# Game_of_Life_v1.net
KiCad netlist of a schematic drawn in EAGLE
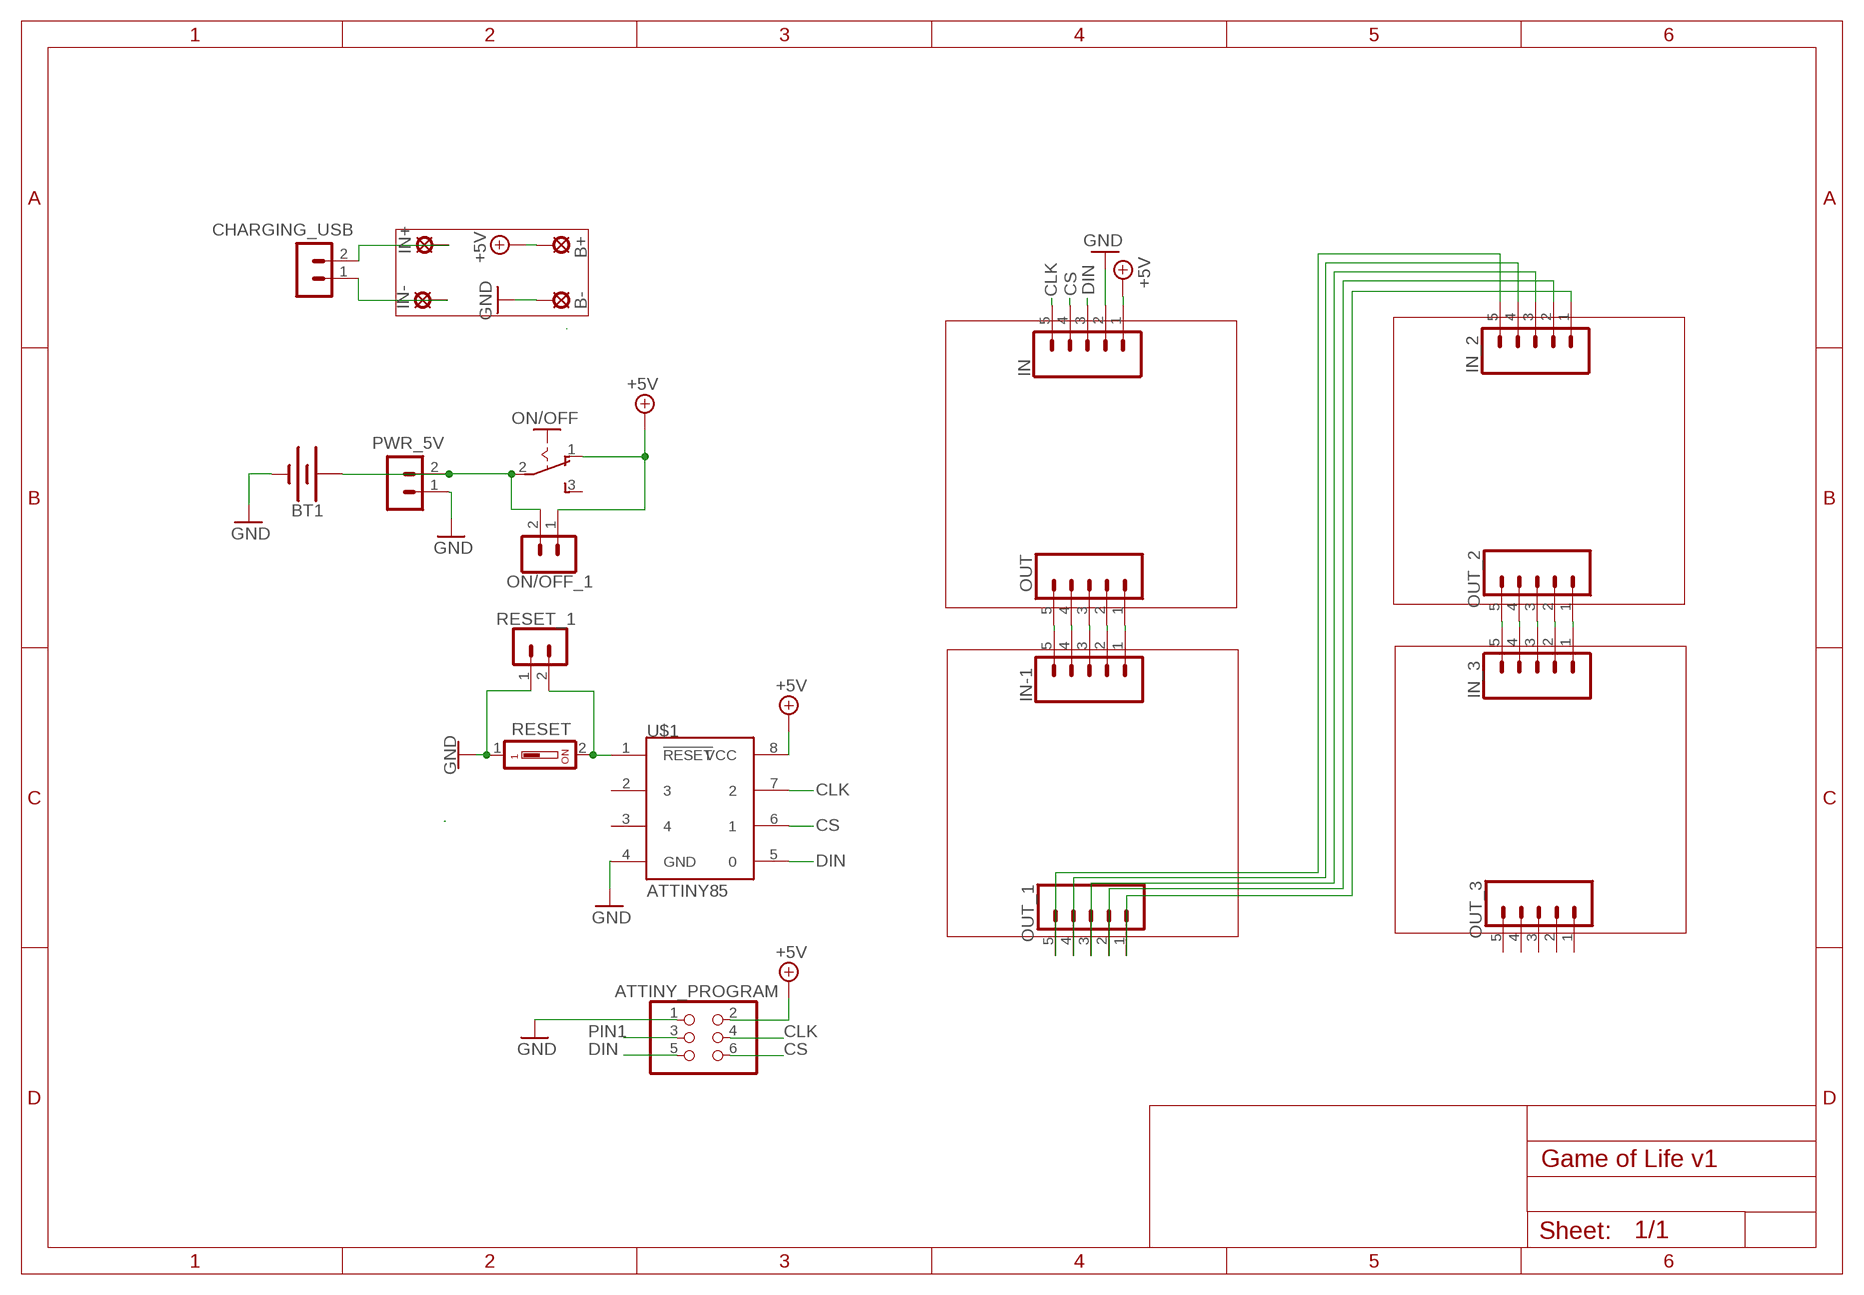
[diagram p0: schematic, sheet 1]

(export (version "E")
  (design (tool "Eeschema 10.0.6"))
  (components
    (comp (ref "ATTINY_PROGRAM")
      (value "PINHD-2X3")
      (footprint "eagle-import:2X03")
      (libsource (lib "eagle-import") (part "PINHD-2X3"))
    )
    (comp (ref "B+")
      (value "LSP11")
      (footprint "eagle-import:LSP11")
      (libsource (lib "eagle-import") (part "LSP11"))
    )
    (comp (ref "B-")
      (value "LSP11")
      (footprint "eagle-import:LSP11")
      (libsource (lib "eagle-import") (part "LSP11"))
    )
    (comp (ref "BT1")
      (value "BATTERY-18650")
      (footprint "eagle-import:BATTERY_18650-HOLDER")
      (libsource (lib "eagle-import") (part "BATTERY-18650"))
    )
    (comp (ref "CHARGING_USB")
      (value "B2B-PH-K-S")
      (footprint "eagle-import:B2B-PH-K-S")
      (libsource (lib "eagle-import") (part "B2B-PH-K-S"))
    )
    (comp (ref "IN")
      (value "CONN_05")
      (footprint "eagle-import:1X05")
      (libsource (lib "eagle-import") (part "CONN_05"))
    )
    (comp (ref "IN+")
      (value "LSP11")
      (footprint "eagle-import:LSP11")
      (libsource (lib "eagle-import") (part "LSP11"))
    )
    (comp (ref "IN-")
      (value "LSP11")
      (footprint "eagle-import:LSP11")
      (libsource (lib "eagle-import") (part "LSP11"))
    )
    (comp (ref "IN-1")
      (value "CONN_05")
      (footprint "eagle-import:1X05")
      (libsource (lib "eagle-import") (part "CONN_05"))
    )
    (comp (ref "IN_2")
      (value "CONN_05")
      (footprint "eagle-import:1X05")
      (libsource (lib "eagle-import") (part "CONN_05"))
    )
    (comp (ref "IN_3")
      (value "CONN_05")
      (footprint "eagle-import:1X05")
      (libsource (lib "eagle-import") (part "CONN_05"))
    )
    (comp (ref "ON/OFF")
      (value "M251")
      (footprint "eagle-import:M251")
      (libsource (lib "eagle-import") (part "M251"))
    )
    (comp (ref "ON/OFF_1")
      (value "B2B-PH-K-S")
      (footprint "eagle-import:B2B-PH-K-S")
      (libsource (lib "eagle-import") (part "B2B-PH-K-S"))
    )
    (comp (ref "OUT")
      (value "CONN_05")
      (footprint "eagle-import:1X05")
      (libsource (lib "eagle-import") (part "CONN_05"))
    )
    (comp (ref "OUT_1")
      (value "CONN_05")
      (footprint "eagle-import:1X05")
      (libsource (lib "eagle-import") (part "CONN_05"))
    )
    (comp (ref "OUT_2")
      (value "CONN_05")
      (footprint "eagle-import:1X05")
      (libsource (lib "eagle-import") (part "CONN_05"))
    )
    (comp (ref "OUT_3")
      (value "CONN_05")
      (footprint "eagle-import:1X05")
      (libsource (lib "eagle-import") (part "CONN_05"))
    )
    (comp (ref "PWR_5V")
      (value "B2B-PH-K-S")
      (footprint "eagle-import:B2B-PH-K-S")
      (libsource (lib "eagle-import") (part "B2B-PH-K-S"))
    )
    (comp (ref "RESET")
      (value "DS01")
      (footprint "eagle-import:DS-01")
      (libsource (lib "eagle-import") (part "DS01"))
    )
    (comp (ref "RESET_1")
      (value "B2B-PH-K-S")
      (footprint "eagle-import:B2B-PH-K-S")
      (libsource (lib "eagle-import") (part "B2B-PH-K-S"))
    )
    (comp (ref "U$1")
      (value "ATTINY85")
      (footprint "eagle-import:8P3")
      (libsource (lib "eagle-import") (part "ATTINY85"))
    )
  )
  (nets
    (net (code "1") (name "+5V") (class "Default")
      (node (ref "ATTINY_PROGRAM") (pin "2") (pinfunction "2_2") (pintype "passive"))
      (node (ref "B+") (pin "MP") (pinfunction "MP_MP") (pintype "passive"))
      (node (ref "IN") (pin "1") (pinfunction "1_1") (pintype "passive"))
      (node (ref "ON/OFF") (pin "1") (pinfunction "O_1") (pintype "passive"))
      (node (ref "ON/OFF_1") (pin "1") (pinfunction "1_1") (pintype "passive"))
      (node (ref "U$1") (pin "8") (pinfunction "VCC_8") (pintype "power_in"))
    )
    (net (code "2") (name "/CLK") (class "Default")
      (node (ref "ATTINY_PROGRAM") (pin "4") (pinfunction "4_4") (pintype "passive"))
      (node (ref "IN") (pin "5") (pinfunction "5_5") (pintype "passive"))
      (node (ref "U$1") (pin "7") (pinfunction "2_7") (pintype "bidirectional"))
    )
    (net (code "3") (name "/CS") (class "Default")
      (node (ref "ATTINY_PROGRAM") (pin "6") (pinfunction "6_6") (pintype "passive"))
      (node (ref "IN") (pin "4") (pinfunction "4_4") (pintype "passive"))
      (node (ref "U$1") (pin "6") (pinfunction "1_6") (pintype "bidirectional"))
    )
    (net (code "4") (name "/DIN") (class "Default")
      (node (ref "ATTINY_PROGRAM") (pin "5") (pinfunction "5_5") (pintype "passive"))
      (node (ref "IN") (pin "3") (pinfunction "3_3") (pintype "passive"))
      (node (ref "U$1") (pin "5") (pinfunction "0_5") (pintype "bidirectional"))
    )
    (net (code "5") (name "/PIN1") (class "Default")
      (node (ref "ATTINY_PROGRAM") (pin "3") (pinfunction "3_3") (pintype "passive"))
      (node (ref "RESET") (pin "2") (pinfunction "2_2") (pintype "passive"))
      (node (ref "RESET_1") (pin "2") (pinfunction "2_2") (pintype "passive"))
      (node (ref "U$1") (pin "1") (pinfunction "~{RESET}_1") (pintype "bidirectional"))
    )
    (net (code "6") (name "GND") (class "Default")
      (node (ref "ATTINY_PROGRAM") (pin "1") (pinfunction "1_1") (pintype "passive"))
      (node (ref "B-") (pin "MP") (pinfunction "MP_MP") (pintype "passive"))
      (node (ref "BT1") (pin "GND@1") (pinfunction "-_GND@1") (pintype "power_in"))
      (node (ref "IN") (pin "2") (pinfunction "2_2") (pintype "passive"))
      (node (ref "PWR_5V") (pin "1") (pinfunction "1_1") (pintype "passive"))
      (node (ref "RESET") (pin "1") (pinfunction "1_1") (pintype "passive"))
      (node (ref "RESET_1") (pin "1") (pinfunction "1_1") (pintype "passive"))
      (node (ref "U$1") (pin "4") (pinfunction "GND_4") (pintype "power_in"))
    )
    (net (code "7") (name "Net-(BT1-+)") (class "Default")
      (node (ref "BT1") (pin "PWR@1") (pinfunction "+_PWR@1") (pintype "power_in"))
      (node (ref "ON/OFF") (pin "2") (pinfunction "P_2") (pintype "passive"))
      (node (ref "ON/OFF_1") (pin "2") (pinfunction "2_2") (pintype "passive"))
      (node (ref "PWR_5V") (pin "2") (pinfunction "2_2") (pintype "passive"))
    )
    (net (code "8") (name "Net-(CHARGING_USB-Pad1)") (class "Default")
      (node (ref "CHARGING_USB") (pin "1") (pinfunction "1_1") (pintype "passive"))
      (node (ref "IN-") (pin "MP") (pinfunction "MP_MP") (pintype "passive"))
    )
    (net (code "9") (name "Net-(CHARGING_USB-Pad2)") (class "Default")
      (node (ref "CHARGING_USB") (pin "2") (pinfunction "2_2") (pintype "passive"))
      (node (ref "IN+") (pin "MP") (pinfunction "MP_MP") (pintype "passive"))
    )
    (net (code "10") (name "Net-(IN-1-Pad1)") (class "Default")
      (node (ref "IN-1") (pin "1") (pinfunction "1_1") (pintype "passive"))
      (node (ref "OUT") (pin "1") (pinfunction "1_1") (pintype "passive"))
    )
    (net (code "11") (name "Net-(IN-1-Pad2)") (class "Default")
      (node (ref "IN-1") (pin "2") (pinfunction "2_2") (pintype "passive"))
      (node (ref "OUT") (pin "2") (pinfunction "2_2") (pintype "passive"))
    )
    (net (code "12") (name "Net-(IN-1-Pad3)") (class "Default")
      (node (ref "IN-1") (pin "3") (pinfunction "3_3") (pintype "passive"))
      (node (ref "OUT") (pin "3") (pinfunction "3_3") (pintype "passive"))
    )
    (net (code "13") (name "Net-(IN-1-Pad4)") (class "Default")
      (node (ref "IN-1") (pin "4") (pinfunction "4_4") (pintype "passive"))
      (node (ref "OUT") (pin "4") (pinfunction "4_4") (pintype "passive"))
    )
    (net (code "14") (name "Net-(IN-1-Pad5)") (class "Default")
      (node (ref "IN-1") (pin "5") (pinfunction "5_5") (pintype "passive"))
      (node (ref "OUT") (pin "5") (pinfunction "5_5") (pintype "passive"))
    )
    (net (code "15") (name "Net-(IN_2-Pad1)") (class "Default")
      (node (ref "IN_2") (pin "1") (pinfunction "1_1") (pintype "passive"))
      (node (ref "OUT_1") (pin "1") (pinfunction "1_1") (pintype "passive"))
    )
    (net (code "16") (name "Net-(IN_2-Pad2)") (class "Default")
      (node (ref "IN_2") (pin "2") (pinfunction "2_2") (pintype "passive"))
      (node (ref "OUT_1") (pin "2") (pinfunction "2_2") (pintype "passive"))
    )
    (net (code "17") (name "Net-(IN_2-Pad3)") (class "Default")
      (node (ref "IN_2") (pin "3") (pinfunction "3_3") (pintype "passive"))
      (node (ref "OUT_1") (pin "3") (pinfunction "3_3") (pintype "passive"))
    )
    (net (code "18") (name "Net-(IN_2-Pad4)") (class "Default")
      (node (ref "IN_2") (pin "4") (pinfunction "4_4") (pintype "passive"))
      (node (ref "OUT_1") (pin "4") (pinfunction "4_4") (pintype "passive"))
    )
    (net (code "19") (name "Net-(IN_2-Pad5)") (class "Default")
      (node (ref "IN_2") (pin "5") (pinfunction "5_5") (pintype "passive"))
      (node (ref "OUT_1") (pin "5") (pinfunction "5_5") (pintype "passive"))
    )
    (net (code "20") (name "Net-(IN_3-Pad1)") (class "Default")
      (node (ref "IN_3") (pin "1") (pinfunction "1_1") (pintype "passive"))
      (node (ref "OUT_2") (pin "1") (pinfunction "1_1") (pintype "passive"))
    )
    (net (code "21") (name "Net-(IN_3-Pad2)") (class "Default")
      (node (ref "IN_3") (pin "2") (pinfunction "2_2") (pintype "passive"))
      (node (ref "OUT_2") (pin "2") (pinfunction "2_2") (pintype "passive"))
    )
    (net (code "22") (name "Net-(IN_3-Pad3)") (class "Default")
      (node (ref "IN_3") (pin "3") (pinfunction "3_3") (pintype "passive"))
      (node (ref "OUT_2") (pin "3") (pinfunction "3_3") (pintype "passive"))
    )
    (net (code "23") (name "Net-(IN_3-Pad4)") (class "Default")
      (node (ref "IN_3") (pin "4") (pinfunction "4_4") (pintype "passive"))
      (node (ref "OUT_2") (pin "4") (pinfunction "4_4") (pintype "passive"))
    )
    (net (code "24") (name "Net-(IN_3-Pad5)") (class "Default")
      (node (ref "IN_3") (pin "5") (pinfunction "5_5") (pintype "passive"))
      (node (ref "OUT_2") (pin "5") (pinfunction "5_5") (pintype "passive"))
    )
    (net (code "25") (name "unconnected-(ON/OFF-S-Pad3)") (class "Default")
      (node (ref "ON/OFF") (pin "3") (pinfunction "S_3") (pintype "passive"))
    )
    (net (code "26") (name "unconnected-(OUT_3-Pad1)") (class "Default")
      (node (ref "OUT_3") (pin "1") (pinfunction "1_1") (pintype "passive"))
    )
    (net (code "27") (name "unconnected-(OUT_3-Pad2)") (class "Default")
      (node (ref "OUT_3") (pin "2") (pinfunction "2_2") (pintype "passive"))
    )
    (net (code "28") (name "unconnected-(OUT_3-Pad3)") (class "Default")
      (node (ref "OUT_3") (pin "3") (pinfunction "3_3") (pintype "passive"))
    )
    (net (code "29") (name "unconnected-(OUT_3-Pad4)") (class "Default")
      (node (ref "OUT_3") (pin "4") (pinfunction "4_4") (pintype "passive"))
    )
    (net (code "30") (name "unconnected-(OUT_3-Pad5)") (class "Default")
      (node (ref "OUT_3") (pin "5") (pinfunction "5_5") (pintype "passive"))
    )
    (net (code "31") (name "unconnected-(U$1-3-Pad2)") (class "Default")
      (node (ref "U$1") (pin "2") (pinfunction "3_2") (pintype "bidirectional"))
    )
    (net (code "32") (name "unconnected-(U$1-4-Pad3)") (class "Default")
      (node (ref "U$1") (pin "3") (pinfunction "4_3") (pintype "bidirectional"))
    )
  )
)
